# low-pass-filter.net
KiCad netlist of a schematic drawn in Altium Designer
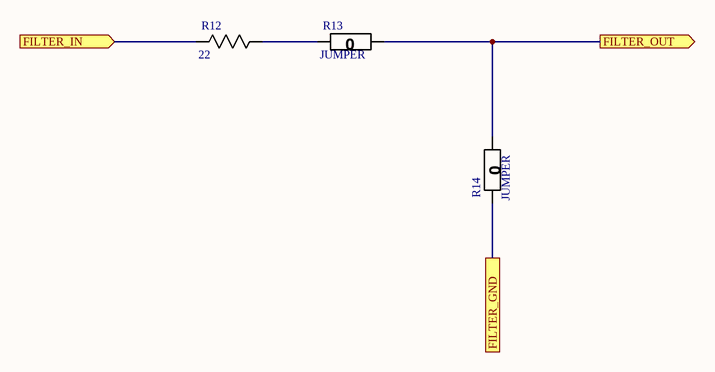
[diagram p0: low-pass-filter.SchDoc]

(export (version "E")
  (design (tool "Eeschema 10.0.6"))
  (components
    (comp (ref "R12")
      (value "22")
      (footprint "0805")
      (description "RES SMD 22 OHM 5% 1/8W 0805")
      (fields (field (name "TOLERANCE") "5%"))
      (libsource (lib "AltiumLibraries") (part "RES 22.0 1/8W"))
    )
    (comp (ref "R13")
      (value "JUMPER")
      (footprint "0805")
      (description "RES SMD 0 OHM JUMPER GENERIC 0805")
      (libsource (lib "AltiumLibraries") (part "RES 0 JUMPER"))
    )
    (comp (ref "R14")
      (value "JUMPER")
      (footprint "0805")
      (description "RES SMD 0 OHM JUMPER GENERIC 0805")
      (libsource (lib "AltiumLibraries") (part "RES 0 JUMPER"))
    )
  )
  (nets
    (net (code "1") (name "/FILTER_GND") (class "Default")
      (node (ref "R14") (pin "2") (pinfunction "R2_2") (pintype "passive"))
    )
    (net (code "2") (name "/FILTER_IN") (class "Default")
      (node (ref "R12") (pin "2") (pinfunction "R2_2") (pintype "passive"))
    )
    (net (code "3") (name "/FILTER_OUT") (class "Default")
      (node (ref "R13") (pin "1") (pinfunction "R1_1") (pintype "passive"))
      (node (ref "R14") (pin "1") (pinfunction "R1_1") (pintype "passive"))
    )
    (net (code "4") (name "Net-(R12-R1)") (class "Default")
      (node (ref "R12") (pin "1") (pinfunction "R1_1") (pintype "passive"))
      (node (ref "R13") (pin "2") (pinfunction "R2_2") (pintype "passive"))
    )
  )
)
